# Project_File.net
KiCad netlist of a schematic drawn in EasyEDA Pro
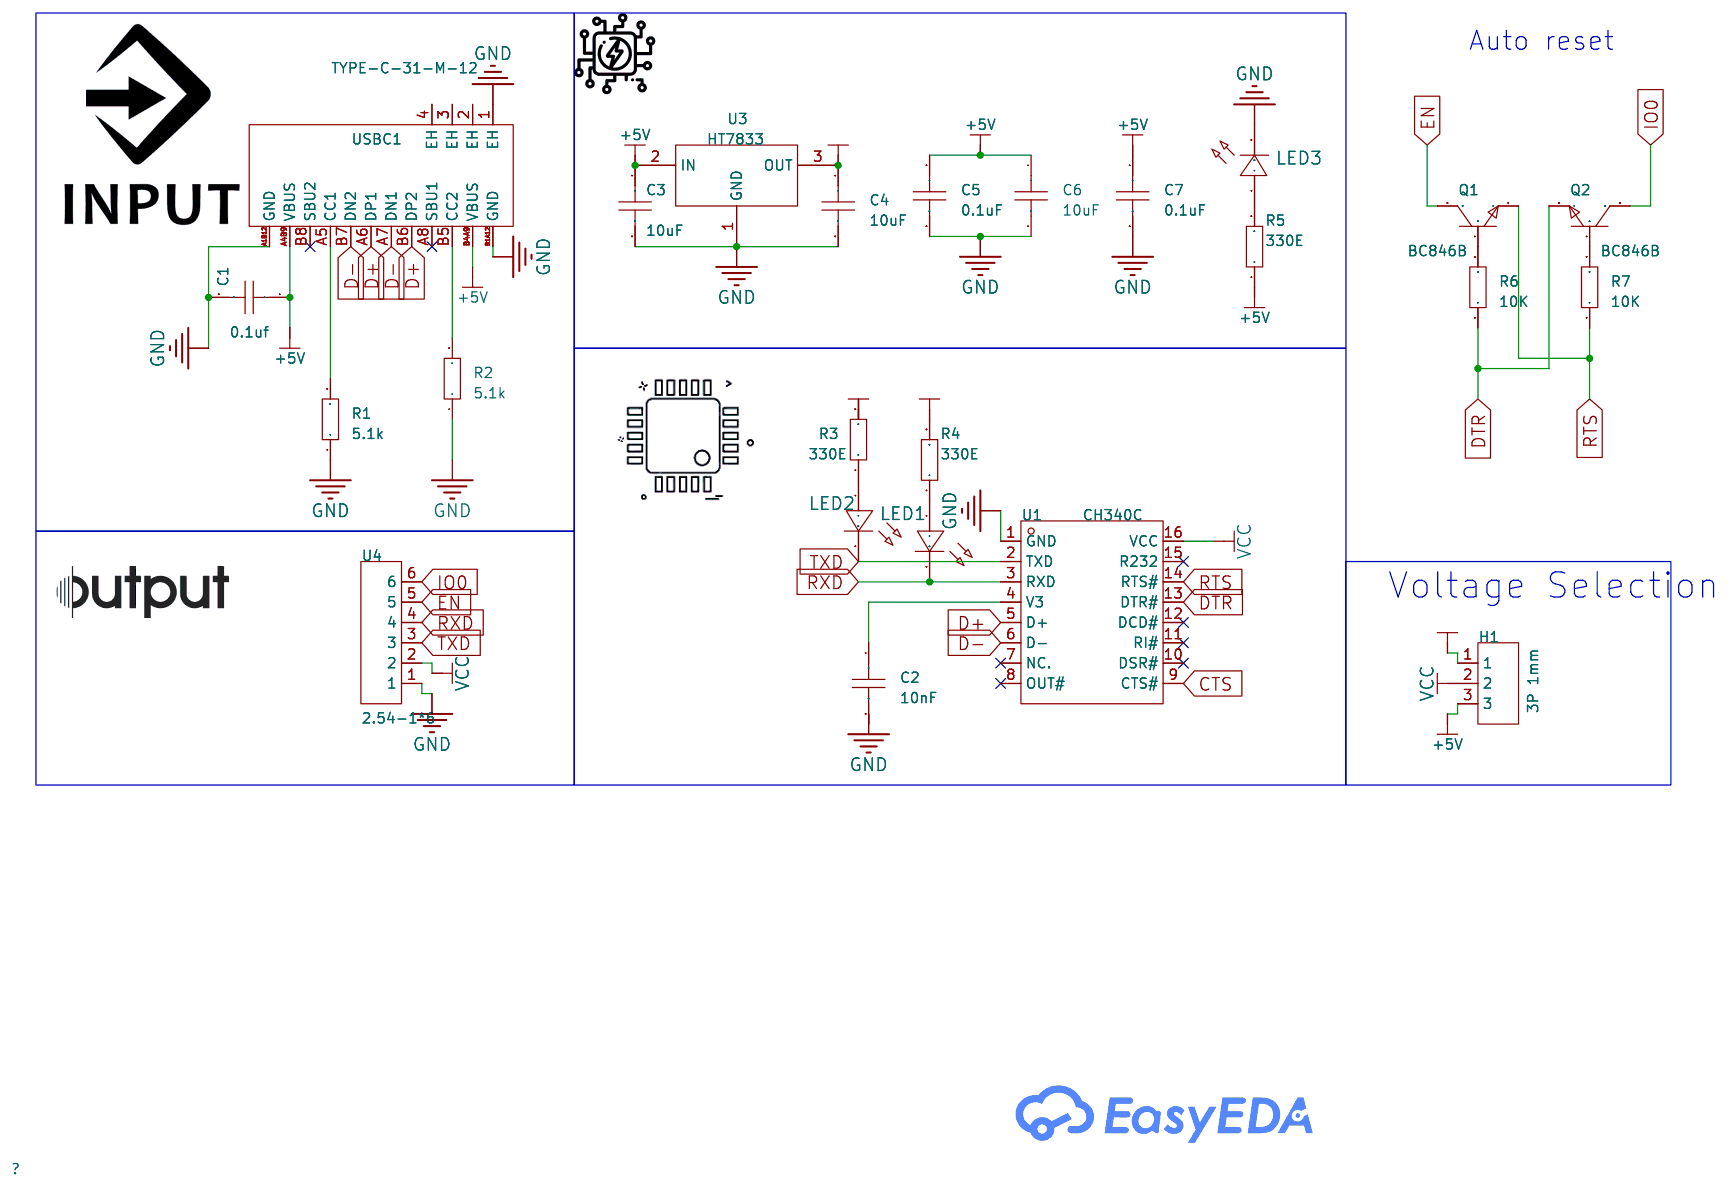
[diagram p0: schematic sheet]

(export (version "E")
  (design (tool "Eeschema 10.0.6"))
  (components
    (comp (ref "C1")
      (value "0.1uf")
      (footprint "easyedapro:C0603")
      (libsource (lib "easyedapro") (part "CAP"))
    )
    (comp (ref "C2")
      (value "10nF")
      (footprint "easyedapro:C0603")
      (libsource (lib "easyedapro") (part "CAP"))
    )
    (comp (ref "C3")
      (value "10uF")
      (footprint "easyedapro:C0603")
      (libsource (lib "easyedapro") (part "CAP"))
    )
    (comp (ref "C4")
      (value "10uF")
      (footprint "easyedapro:C0603")
      (libsource (lib "easyedapro") (part "CAP"))
    )
    (comp (ref "C5")
      (value "0.1uF")
      (footprint "easyedapro:C0603")
      (libsource (lib "easyedapro") (part "CAP"))
    )
    (comp (ref "C6")
      (value "10uF")
      (footprint "easyedapro:C0603")
      (libsource (lib "easyedapro") (part "CAP"))
    )
    (comp (ref "C7")
      (value "0.1uF")
      (footprint "easyedapro:C0603")
      (libsource (lib "easyedapro") (part "CAP"))
    )
    (comp (ref "H1")
      (value "3P 1mm")
      (footprint "easyedapro:HDR-TH_3P-P1.00-V-M")
      (fields (field (name "Manufacturer") "CHIN-BAN(勤本)"))
      (libsource (lib "easyedapro") (part "P2C03A-201020-B1P"))
    )
    (comp (ref "LED1")
      (value "~")
      (footprint "easyedapro:LED0402-RD_YELLOW")
      (libsource (lib "easyedapro") (part "LED_R"))
    )
    (comp (ref "LED2")
      (value "~")
      (footprint "easyedapro:LED0402-RD_YELLOW")
      (libsource (lib "easyedapro") (part "LED_R"))
    )
    (comp (ref "LED3")
      (value "~")
      (footprint "easyedapro:LED0402-RD_YELLOW")
      (libsource (lib "easyedapro") (part "LED_R"))
    )
    (comp (ref "Q1")
      (value "BC846B")
      (footprint "easyedapro:SOT-23-3_L2.9-W1.3-P1.90-LS2.4-BR")
      (fields (field (name "Manufacturer") "R+O(宏嘉诚)"))
      (libsource (lib "easyedapro") (part "BC846B_C20069134"))
    )
    (comp (ref "Q2")
      (value "BC846B")
      (footprint "easyedapro:SOT-23-3_L2.9-W1.3-P1.90-LS2.4-BR")
      (fields (field (name "Manufacturer") "R+O(宏嘉诚)"))
      (libsource (lib "easyedapro") (part "BC846B_C20069134"))
    )
    (comp (ref "R1")
      (value "5.1k")
      (footprint "easyedapro:R0603")
      (libsource (lib "easyedapro") (part "Res"))
    )
    (comp (ref "R2")
      (value "5.1k")
      (footprint "easyedapro:R0603")
      (libsource (lib "easyedapro") (part "Res"))
    )
    (comp (ref "R3")
      (value "330E")
      (footprint "easyedapro:R0603")
      (libsource (lib "easyedapro") (part "Res"))
    )
    (comp (ref "R4")
      (value "330E")
      (footprint "easyedapro:R0603")
      (libsource (lib "easyedapro") (part "Res"))
    )
    (comp (ref "R5")
      (value "330E")
      (footprint "easyedapro:R0603")
      (libsource (lib "easyedapro") (part "Res"))
    )
    (comp (ref "R6") (value "10K") (footprint "easyedapro:R0603") (libsource (lib "easyedapro") (part "Res")))
    (comp (ref "R7") (value "10K") (footprint "easyedapro:R0603") (libsource (lib "easyedapro") (part "Res")))
    (comp (ref "U1")
      (value "CH340C")
      (footprint "easyedapro:SOP-16_L10.0-W3.9-P1.27-LS6.0-BL")
      (fields (field (name "Manufacturer") "WCH(南京沁恒)"))
      (libsource (lib "easyedapro") (part "CH340C"))
    )
    (comp (ref "U3")
      (value "HT7833")
      (footprint "easyedapro:SOT-89_L4.5-W2.5-P1.50-LS4.2-BR")
      (fields (field (name "Manufacturer") "HOLTEK(合泰/盛群)"))
      (libsource (lib "easyedapro") (part "HT7833"))
    )
    (comp (ref "U4")
      (value "2.54-1*6")
      (footprint "easyedapro:HDR-TH_6P-P2.54-V-M")
      (fields (field (name "Manufacturer") "ZHOURI(洲日)"))
      (libsource (lib "easyedapro") (part "2.54-1*6"))
    )
    (comp (ref "USBC1")
      (value "TYPE-C-31-M-12")
      (footprint "easyedapro:USB-C_SMD-TYPE-C-31-M-12_1")
      (fields (field (name "Manufacturer") "韩国韩荣"))
      (libsource (lib "easyedapro") (part "TYPE-C-31-M-12"))
    )
  )
  (nets
    (net (code "1") (name "+5V") (class "Default")
      (node (ref "C1") (pin "1") (pinfunction "1_1") (pintype "input"))
      (node (ref "C3") (pin "1") (pinfunction "1_1") (pintype "input"))
      (node (ref "C5") (pin "1") (pinfunction "1_1") (pintype "input"))
      (node (ref "C6") (pin "1") (pinfunction "1_1") (pintype "input"))
      (node (ref "C7") (pin "1") (pinfunction "1_1") (pintype "input"))
      (node (ref "H1") (pin "3") (pinfunction "3_3") (pintype "unspecified"))
      (node (ref "R5") (pin "1") (pinfunction "1_1") (pintype "input"))
      (node (ref "U3") (pin "2") (pinfunction "IN_2") (pintype "unspecified"))
      (node (ref "USBC1") (pin "A4B9") (pinfunction "VBUS_A4B9") (pintype "unspecified"))
      (node (ref "USBC1") (pin "B4A9") (pinfunction "VBUS_B4A9") (pintype "unspecified"))
    )
    (net (code "2") (name "3.3V") (class "Default")
      (node (ref "C4") (pin "1") (pinfunction "1_1") (pintype "input"))
      (node (ref "H1") (pin "1") (pinfunction "1_1") (pintype "unspecified"))
      (node (ref "R3") (pin "2") (pinfunction "2_2") (pintype "input"))
      (node (ref "R4") (pin "2") (pinfunction "2_2") (pintype "input"))
      (node (ref "U3") (pin "3") (pinfunction "OUT_3") (pintype "unspecified"))
    )
    (net (code "3") (name "CTS") (class "Default")
      (node (ref "U1") (pin "9") (pinfunction "CTS#_9") (pintype "unspecified"))
    )
    (net (code "4") (name "D+") (class "Default")
      (node (ref "U1") (pin "5") (pinfunction "D+_5") (pintype "unspecified"))
      (node (ref "USBC1") (pin "A6") (pinfunction "DP1_A6") (pintype "unspecified"))
      (node (ref "USBC1") (pin "B6") (pinfunction "DP2_B6") (pintype "unspecified"))
    )
    (net (code "5") (name "D-") (class "Default")
      (node (ref "U1") (pin "6") (pinfunction "D-_6") (pintype "unspecified"))
      (node (ref "USBC1") (pin "A7") (pinfunction "DN1_A7") (pintype "unspecified"))
      (node (ref "USBC1") (pin "B7") (pinfunction "DN2_B7") (pintype "unspecified"))
    )
    (net (code "6") (name "DTR") (class "Default")
      (node (ref "Q2") (pin "2") (pinfunction "E_2") (pintype "input"))
      (node (ref "R6") (pin "1") (pinfunction "1_1") (pintype "input"))
      (node (ref "U1") (pin "13") (pinfunction "DTR#_13") (pintype "unspecified"))
    )
    (net (code "7") (name "EN") (class "Default")
      (node (ref "Q1") (pin "3") (pinfunction "C_3") (pintype "input"))
      (node (ref "U4") (pin "5") (pinfunction "5_5") (pintype "unspecified"))
    )
    (net (code "8") (name "GND") (class "Default")
      (node (ref "C1") (pin "2") (pinfunction "2_2") (pintype "input"))
      (node (ref "C2") (pin "2") (pinfunction "2_2") (pintype "input"))
      (node (ref "C3") (pin "2") (pinfunction "2_2") (pintype "input"))
      (node (ref "C4") (pin "2") (pinfunction "2_2") (pintype "input"))
      (node (ref "C5") (pin "2") (pinfunction "2_2") (pintype "input"))
      (node (ref "C6") (pin "2") (pinfunction "2_2") (pintype "input"))
      (node (ref "C7") (pin "2") (pinfunction "2_2") (pintype "input"))
      (node (ref "LED3") (pin "2") (pinfunction "C_2") (pintype "input"))
      (node (ref "R1") (pin "1") (pinfunction "1_1") (pintype "input"))
      (node (ref "R2") (pin "1") (pinfunction "1_1") (pintype "input"))
      (node (ref "U1") (pin "1") (pinfunction "GND_1") (pintype "unspecified"))
      (node (ref "U3") (pin "1") (pinfunction "GND_1") (pintype "unspecified"))
      (node (ref "U4") (pin "1") (pinfunction "1_1") (pintype "unspecified"))
      (node (ref "USBC1") (pin "1") (pinfunction "EH_1") (pintype "unspecified"))
      (node (ref "USBC1") (pin "A1B12") (pinfunction "GND_A1B12") (pintype "unspecified"))
      (node (ref "USBC1") (pin "B1A12") (pinfunction "GND_B1A12") (pintype "unspecified"))
    )
    (net (code "9") (name "IO0") (class "Default")
      (node (ref "Q2") (pin "3") (pinfunction "C_3") (pintype "input"))
      (node (ref "U4") (pin "6") (pinfunction "6_6") (pintype "unspecified"))
    )
    (net (code "10") (name "Net-(LED1-A)") (class "Default")
      (node (ref "LED1") (pin "1") (pinfunction "A_1") (pintype "input"))
      (node (ref "R4") (pin "1") (pinfunction "1_1") (pintype "input"))
    )
    (net (code "11") (name "Net-(LED2-A)") (class "Default")
      (node (ref "LED2") (pin "1") (pinfunction "A_1") (pintype "input"))
      (node (ref "R3") (pin "1") (pinfunction "1_1") (pintype "input"))
    )
    (net (code "12") (name "Net-(LED3-A)") (class "Default")
      (node (ref "LED3") (pin "1") (pinfunction "A_1") (pintype "input"))
      (node (ref "R5") (pin "2") (pinfunction "2_2") (pintype "input"))
    )
    (net (code "13") (name "Net-(Q1-B)") (class "Default")
      (node (ref "Q1") (pin "1") (pinfunction "B_1") (pintype "input"))
      (node (ref "R6") (pin "2") (pinfunction "2_2") (pintype "input"))
    )
    (net (code "14") (name "Net-(Q2-B)") (class "Default")
      (node (ref "Q2") (pin "1") (pinfunction "B_1") (pintype "input"))
      (node (ref "R7") (pin "2") (pinfunction "2_2") (pintype "input"))
    )
    (net (code "15") (name "Net-(U1-V3)") (class "Default")
      (node (ref "C2") (pin "1") (pinfunction "1_1") (pintype "input"))
      (node (ref "U1") (pin "4") (pinfunction "V3_4") (pintype "unspecified"))
    )
    (net (code "16") (name "Net-(USBC1-CC1)") (class "Default")
      (node (ref "R1") (pin "2") (pinfunction "2_2") (pintype "input"))
      (node (ref "USBC1") (pin "A5") (pinfunction "CC1_A5") (pintype "unspecified"))
    )
    (net (code "17") (name "Net-(USBC1-CC2)") (class "Default")
      (node (ref "R2") (pin "2") (pinfunction "2_2") (pintype "input"))
      (node (ref "USBC1") (pin "B5") (pinfunction "CC2_B5") (pintype "unspecified"))
    )
    (net (code "18") (name "RTS") (class "Default")
      (node (ref "Q1") (pin "2") (pinfunction "E_2") (pintype "input"))
      (node (ref "R7") (pin "1") (pinfunction "1_1") (pintype "input"))
      (node (ref "U1") (pin "14") (pinfunction "RTS#_14") (pintype "unspecified"))
    )
    (net (code "19") (name "RXD") (class "Default")
      (node (ref "LED1") (pin "2") (pinfunction "C_2") (pintype "input"))
      (node (ref "U1") (pin "3") (pinfunction "RXD_3") (pintype "unspecified"))
      (node (ref "U4") (pin "4") (pinfunction "4_4") (pintype "unspecified"))
    )
    (net (code "20") (name "TXD") (class "Default")
      (node (ref "LED2") (pin "2") (pinfunction "C_2") (pintype "input"))
      (node (ref "U1") (pin "2") (pinfunction "TXD_2") (pintype "unspecified"))
      (node (ref "U4") (pin "3") (pinfunction "3_3") (pintype "unspecified"))
    )
    (net (code "21") (name "VCC") (class "Default")
      (node (ref "H1") (pin "2") (pinfunction "2_2") (pintype "unspecified"))
      (node (ref "U1") (pin "16") (pinfunction "VCC_16") (pintype "unspecified"))
      (node (ref "U4") (pin "2") (pinfunction "2_2") (pintype "unspecified"))
    )
    (net (code "22") (name "unconnected-(U1-DCD#-Pad12)") (class "Default")
      (node (ref "U1") (pin "12") (pinfunction "DCD#_12") (pintype "unspecified+no_connect"))
    )
    (net (code "23") (name "unconnected-(U1-DSR#-Pad10)") (class "Default")
      (node (ref "U1") (pin "10") (pinfunction "DSR#_10") (pintype "unspecified+no_connect"))
    )
    (net (code "24") (name "unconnected-(U1-NC.-Pad7)") (class "Default")
      (node (ref "U1") (pin "7") (pinfunction "NC._7") (pintype "unspecified+no_connect"))
    )
    (net (code "25") (name "unconnected-(U1-OUT#-Pad8)") (class "Default")
      (node (ref "U1") (pin "8") (pinfunction "OUT#_8") (pintype "unspecified+no_connect"))
    )
    (net (code "26") (name "unconnected-(U1-R232-Pad15)") (class "Default")
      (node (ref "U1") (pin "15") (pinfunction "R232_15") (pintype "unspecified+no_connect"))
    )
    (net (code "27") (name "unconnected-(U1-RI#-Pad11)") (class "Default")
      (node (ref "U1") (pin "11") (pinfunction "RI#_11") (pintype "unspecified+no_connect"))
    )
    (net (code "28") (name "unconnected-(USBC1-EH-Pad2)") (class "Default")
      (node (ref "USBC1") (pin "2") (pinfunction "EH_2") (pintype "unspecified"))
    )
    (net (code "29") (name "unconnected-(USBC1-EH-Pad3)") (class "Default")
      (node (ref "USBC1") (pin "3") (pinfunction "EH_3") (pintype "unspecified"))
    )
    (net (code "30") (name "unconnected-(USBC1-EH-Pad4)") (class "Default")
      (node (ref "USBC1") (pin "4") (pinfunction "EH_4") (pintype "unspecified"))
    )
    (net (code "31") (name "unconnected-(USBC1-SBU1-PadA8)") (class "Default")
      (node (ref "USBC1") (pin "A8") (pinfunction "SBU1_A8") (pintype "unspecified+no_connect"))
    )
    (net (code "32") (name "unconnected-(USBC1-SBU2-PadB8)") (class "Default")
      (node (ref "USBC1") (pin "B8") (pinfunction "SBU2_B8") (pintype "unspecified+no_connect"))
    )
  )
)
